# filter.net
KiCad netlist of a schematic drawn in Altium Designer
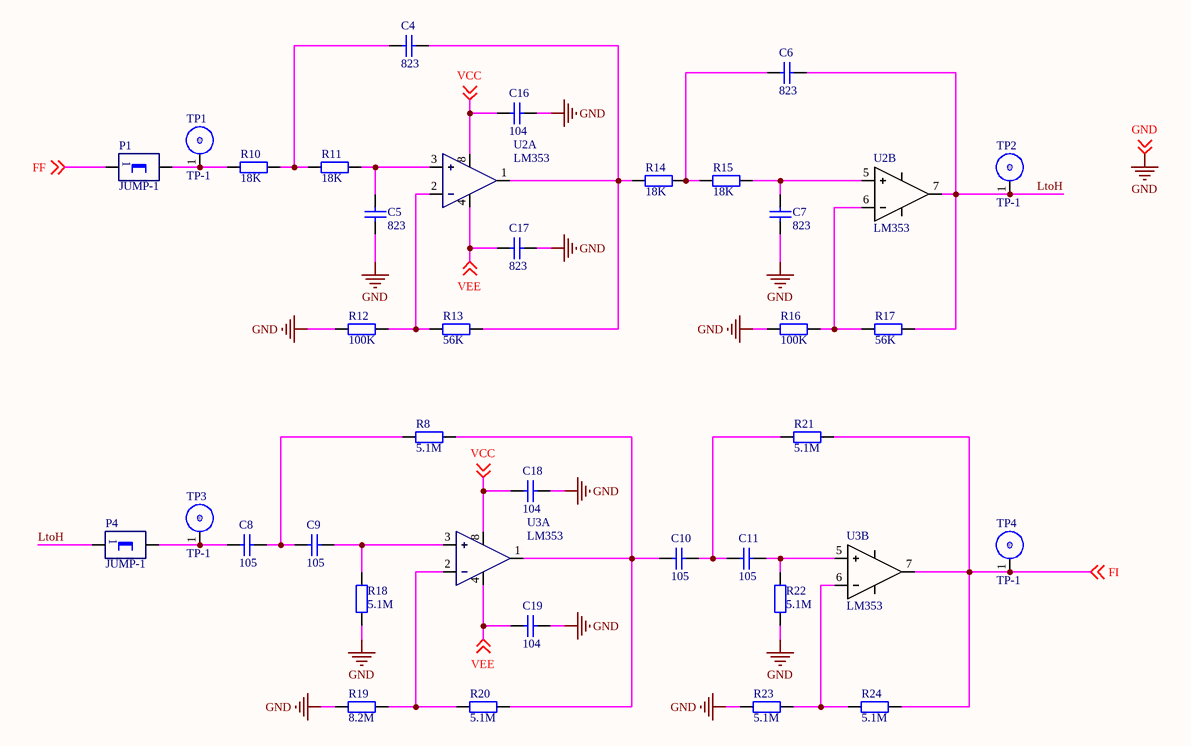
[diagram p0: filter.SchDoc]

(export (version "E")
  (design (tool "Eeschema 10.0.6"))
  (components
    (comp (ref "C4")
      (value "823")
      (footprint "C2")
      (description "Capacitor")
      (fields (field (name "PUBLISHER") "Altium Limited"))
      (libsource (lib "ECG") (part "Cap"))
    )
    (comp (ref "C5")
      (value "823")
      (footprint "C2")
      (description "Capacitor")
      (fields (field (name "PUBLISHER") "Altium Limited"))
      (libsource (lib "ECG") (part "Cap"))
    )
    (comp (ref "C6")
      (value "823")
      (footprint "C2")
      (description "Capacitor")
      (fields (field (name "PUBLISHER") "Altium Limited"))
      (libsource (lib "ECG") (part "Cap"))
    )
    (comp (ref "C7")
      (value "823")
      (footprint "C2")
      (description "Capacitor")
      (fields (field (name "PUBLISHER") "Altium Limited"))
      (libsource (lib "ECG") (part "Cap"))
    )
    (comp (ref "C8")
      (value "105")
      (footprint "C2")
      (description "Capacitor")
      (fields (field (name "PUBLISHER") "Altium Limited"))
      (libsource (lib "ECG") (part "Cap"))
    )
    (comp (ref "C9")
      (value "105")
      (footprint "C2")
      (description "Capacitor")
      (fields (field (name "PUBLISHER") "Altium Limited"))
      (libsource (lib "ECG") (part "Cap"))
    )
    (comp (ref "C10")
      (value "105")
      (footprint "C2")
      (description "Capacitor")
      (fields (field (name "PUBLISHER") "Altium Limited"))
      (libsource (lib "ECG") (part "Cap"))
    )
    (comp (ref "C11")
      (value "105")
      (footprint "C2")
      (description "Capacitor")
      (fields (field (name "PUBLISHER") "Altium Limited"))
      (libsource (lib "ECG") (part "Cap"))
    )
    (comp (ref "C16")
      (value "104")
      (footprint "C2")
      (description "Capacitor")
      (fields (field (name "PUBLISHER") "Altium Limited"))
      (libsource (lib "ECG") (part "Cap"))
    )
    (comp (ref "C17")
      (value "823")
      (footprint "C2")
      (description "Capacitor")
      (fields (field (name "PUBLISHER") "Altium Limited"))
      (libsource (lib "ECG") (part "Cap"))
    )
    (comp (ref "C18")
      (value "104")
      (footprint "C2")
      (description "Capacitor")
      (fields (field (name "PUBLISHER") "Altium Limited"))
      (libsource (lib "ECG") (part "Cap"))
    )
    (comp (ref "C19")
      (value "104")
      (footprint "C2")
      (description "Capacitor")
      (fields (field (name "PUBLISHER") "Altium Limited"))
      (libsource (lib "ECG") (part "Cap"))
    )
    (comp (ref "P1") (value "JUMP-1") (footprint "SIP2") (libsource (lib "ECG") (part "JUMP-1")))
    (comp (ref "P4") (value "JUMP-1") (footprint "SIP2") (libsource (lib "ECG") (part "JUMP-1")))
    (comp (ref "R8")
      (value "5.1M")
      (footprint "AXIAL-0.3")
      (description "Resistor")
      (fields (field (name "PUBLISHER") "Altium Limited"))
      (libsource (lib "") (part "Res2_1"))
    )
    (comp (ref "R10")
      (value "18K")
      (footprint "AXIAL-0.3")
      (description "Resistor")
      (fields (field (name "PUBLISHER") "Altium Limited"))
      (libsource (lib "") (part "Res2_1"))
    )
    (comp (ref "R11")
      (value "18K")
      (footprint "AXIAL-0.3")
      (description "Resistor")
      (fields (field (name "PUBLISHER") "Altium Limited"))
      (libsource (lib "") (part "Res2_1"))
    )
    (comp (ref "R12")
      (value "100K")
      (footprint "AXIAL-0.3")
      (description "Resistor")
      (fields (field (name "PUBLISHER") "Altium Limited"))
      (libsource (lib "") (part "Res2_1"))
    )
    (comp (ref "R13")
      (value "56K")
      (footprint "AXIAL-0.3")
      (description "Resistor")
      (fields (field (name "PUBLISHER") "Altium Limited"))
      (libsource (lib "") (part "Res2_1"))
    )
    (comp (ref "R14")
      (value "18K")
      (footprint "AXIAL-0.3")
      (description "Resistor")
      (fields (field (name "PUBLISHER") "Altium Limited"))
      (libsource (lib "") (part "Res2_1"))
    )
    (comp (ref "R15")
      (value "18K")
      (footprint "AXIAL-0.3")
      (description "Resistor")
      (fields (field (name "PUBLISHER") "Altium Limited"))
      (libsource (lib "") (part "Res2_1"))
    )
    (comp (ref "R16")
      (value "100K")
      (footprint "AXIAL-0.3")
      (description "Resistor")
      (fields (field (name "PUBLISHER") "Altium Limited"))
      (libsource (lib "") (part "Res2_1"))
    )
    (comp (ref "R17")
      (value "56K")
      (footprint "AXIAL-0.3")
      (description "Resistor")
      (fields (field (name "PUBLISHER") "Altium Limited"))
      (libsource (lib "") (part "Res2_1"))
    )
    (comp (ref "R18")
      (value "5.1M")
      (footprint "AXIAL-0.3")
      (description "Resistor")
      (fields (field (name "PUBLISHER") "Altium Limited"))
      (libsource (lib "ECG") (part "Res2"))
    )
    (comp (ref "R19")
      (value "8.2M")
      (footprint "AXIAL-0.3")
      (description "Resistor")
      (fields (field (name "PUBLISHER") "Altium Limited"))
      (libsource (lib "") (part "Res2_1"))
    )
    (comp (ref "R20")
      (value "5.1M")
      (footprint "AXIAL-0.3")
      (description "Resistor")
      (fields (field (name "PUBLISHER") "Altium Limited"))
      (libsource (lib "") (part "Res2_1"))
    )
    (comp (ref "R21")
      (value "5.1M")
      (footprint "AXIAL-0.3")
      (description "Resistor")
      (fields (field (name "PUBLISHER") "Altium Limited"))
      (libsource (lib "") (part "Res2_1"))
    )
    (comp (ref "R22")
      (value "5.1M")
      (footprint "AXIAL-0.3")
      (description "Resistor")
      (fields (field (name "PUBLISHER") "Altium Limited"))
      (libsource (lib "ECG") (part "Res2"))
    )
    (comp (ref "R23")
      (value "5.1M")
      (footprint "AXIAL-0.3")
      (description "Resistor")
      (fields (field (name "PUBLISHER") "Altium Limited"))
      (libsource (lib "") (part "Res2_1"))
    )
    (comp (ref "R24")
      (value "5.1M")
      (footprint "AXIAL-0.3")
      (description "Resistor")
      (fields (field (name "PUBLISHER") "Altium Limited"))
      (libsource (lib "") (part "Res2_1"))
    )
    (comp (ref "TP1") (value "TP-1") (footprint "tp-1-1") (libsource (lib "ECG") (part "TP-1")))
    (comp (ref "TP2") (value "TP-1") (footprint "tp-1-1") (libsource (lib "ECG") (part "TP-1")))
    (comp (ref "TP3") (value "TP-1") (footprint "tp-1-1") (libsource (lib "ECG") (part "TP-1")))
    (comp (ref "TP4") (value "TP-1") (footprint "tp-1-1") (libsource (lib "ECG") (part "TP-1")))
    (comp (ref "U2") (value "LM353") (footprint "DIP8") (libsource (lib "ECG") (part "LM353")))
    (comp (ref "U3") (value "LM353") (footprint "DIP8") (libsource (lib "ECG") (part "LM353")))
  )
  (nets
    (net (code "1") (name "/LtoH") (class "Default")
      (node (ref "C6") (pin "2") (pinfunction "2_2") (pintype "passive"))
      (node (ref "P4") (pin "1") (pinfunction "1_1") (pintype "passive"))
      (node (ref "R17") (pin "2") (pinfunction "2_2") (pintype "passive"))
      (node (ref "TP2") (pin "1") (pintype "passive"))
      (node (ref "U2") (pin "7") (pinfunction "7_7") (pintype "passive"))
    )
    (net (code "2") (name "FF") (class "Default")
      (node (ref "P1") (pin "1") (pinfunction "1_1") (pintype "passive"))
    )
    (net (code "3") (name "FI") (class "Default")
      (node (ref "R21") (pin "2") (pinfunction "2_2") (pintype "passive"))
      (node (ref "R24") (pin "2") (pinfunction "2_2") (pintype "passive"))
      (node (ref "TP4") (pin "1") (pintype "passive"))
      (node (ref "U3") (pin "7") (pinfunction "7_7") (pintype "passive"))
    )
    (net (code "4") (name "GND") (class "Default")
      (node (ref "C16") (pin "2") (pinfunction "2_2") (pintype "passive"))
      (node (ref "C17") (pin "2") (pinfunction "2_2") (pintype "passive"))
      (node (ref "C18") (pin "2") (pinfunction "2_2") (pintype "passive"))
      (node (ref "C19") (pin "2") (pinfunction "2_2") (pintype "passive"))
      (node (ref "C5") (pin "1") (pinfunction "1_1") (pintype "passive"))
      (node (ref "C7") (pin "1") (pinfunction "1_1") (pintype "passive"))
      (node (ref "R12") (pin "1") (pinfunction "1_1") (pintype "passive"))
      (node (ref "R16") (pin "1") (pinfunction "1_1") (pintype "passive"))
      (node (ref "R18") (pin "1") (pinfunction "1_1") (pintype "passive"))
      (node (ref "R19") (pin "1") (pinfunction "1_1") (pintype "passive"))
      (node (ref "R22") (pin "1") (pinfunction "1_1") (pintype "passive"))
      (node (ref "R23") (pin "1") (pinfunction "1_1") (pintype "passive"))
    )
    (net (code "5") (name "Net-(C4-Pad1)") (class "Default")
      (node (ref "C4") (pin "1") (pinfunction "1_1") (pintype "passive"))
      (node (ref "R10") (pin "2") (pinfunction "2_2") (pintype "passive"))
      (node (ref "R11") (pin "1") (pinfunction "1_1") (pintype "passive"))
    )
    (net (code "6") (name "Net-(C4-Pad2)") (class "Default")
      (node (ref "C4") (pin "2") (pinfunction "2_2") (pintype "passive"))
      (node (ref "R13") (pin "2") (pinfunction "2_2") (pintype "passive"))
      (node (ref "R14") (pin "1") (pinfunction "1_1") (pintype "passive"))
      (node (ref "U2") (pin "1") (pinfunction "1_1") (pintype "passive"))
    )
    (net (code "7") (name "Net-(C5-Pad2)") (class "Default")
      (node (ref "C5") (pin "2") (pinfunction "2_2") (pintype "passive"))
      (node (ref "R11") (pin "2") (pinfunction "2_2") (pintype "passive"))
      (node (ref "U2") (pin "3") (pinfunction "3_3") (pintype "passive"))
    )
    (net (code "8") (name "Net-(C6-Pad1)") (class "Default")
      (node (ref "C6") (pin "1") (pinfunction "1_1") (pintype "passive"))
      (node (ref "R14") (pin "2") (pinfunction "2_2") (pintype "passive"))
      (node (ref "R15") (pin "1") (pinfunction "1_1") (pintype "passive"))
    )
    (net (code "9") (name "Net-(C7-Pad2)") (class "Default")
      (node (ref "C7") (pin "2") (pinfunction "2_2") (pintype "passive"))
      (node (ref "R15") (pin "2") (pinfunction "2_2") (pintype "passive"))
      (node (ref "U2") (pin "5") (pinfunction "5_5") (pintype "passive"))
    )
    (net (code "10") (name "Net-(C8-Pad1)") (class "Default")
      (node (ref "C8") (pin "1") (pinfunction "1_1") (pintype "passive"))
      (node (ref "P4") (pin "2") (pintype "passive"))
      (node (ref "TP3") (pin "1") (pintype "passive"))
    )
    (net (code "11") (name "Net-(C8-Pad2)") (class "Default")
      (node (ref "C8") (pin "2") (pinfunction "2_2") (pintype "passive"))
      (node (ref "C9") (pin "1") (pinfunction "1_1") (pintype "passive"))
      (node (ref "R8") (pin "1") (pinfunction "1_1") (pintype "passive"))
    )
    (net (code "12") (name "Net-(C9-Pad2)") (class "Default")
      (node (ref "C9") (pin "2") (pinfunction "2_2") (pintype "passive"))
      (node (ref "R18") (pin "2") (pinfunction "2_2") (pintype "passive"))
      (node (ref "U3") (pin "3") (pinfunction "3_3") (pintype "passive"))
    )
    (net (code "13") (name "Net-(C10-Pad1)") (class "Default")
      (node (ref "C10") (pin "1") (pinfunction "1_1") (pintype "passive"))
      (node (ref "R20") (pin "2") (pinfunction "2_2") (pintype "passive"))
      (node (ref "R8") (pin "2") (pinfunction "2_2") (pintype "passive"))
      (node (ref "U3") (pin "1") (pinfunction "1_1") (pintype "passive"))
    )
    (net (code "14") (name "Net-(C10-Pad2)") (class "Default")
      (node (ref "C10") (pin "2") (pinfunction "2_2") (pintype "passive"))
      (node (ref "C11") (pin "1") (pinfunction "1_1") (pintype "passive"))
      (node (ref "R21") (pin "1") (pinfunction "1_1") (pintype "passive"))
    )
    (net (code "15") (name "Net-(C11-Pad2)") (class "Default")
      (node (ref "C11") (pin "2") (pinfunction "2_2") (pintype "passive"))
      (node (ref "R22") (pin "2") (pinfunction "2_2") (pintype "passive"))
      (node (ref "U3") (pin "5") (pinfunction "5_5") (pintype "passive"))
    )
    (net (code "16") (name "Net-(P1-Pad2)") (class "Default")
      (node (ref "P1") (pin "2") (pintype "passive"))
      (node (ref "R10") (pin "1") (pinfunction "1_1") (pintype "passive"))
      (node (ref "TP1") (pin "1") (pintype "passive"))
    )
    (net (code "17") (name "Net-(R12-Pad2)") (class "Default")
      (node (ref "R12") (pin "2") (pinfunction "2_2") (pintype "passive"))
      (node (ref "R13") (pin "1") (pinfunction "1_1") (pintype "passive"))
      (node (ref "U2") (pin "2") (pinfunction "2_2") (pintype "passive"))
    )
    (net (code "18") (name "Net-(R16-Pad2)") (class "Default")
      (node (ref "R16") (pin "2") (pinfunction "2_2") (pintype "passive"))
      (node (ref "R17") (pin "1") (pinfunction "1_1") (pintype "passive"))
      (node (ref "U2") (pin "6") (pinfunction "6_6") (pintype "passive"))
    )
    (net (code "19") (name "Net-(R19-Pad2)") (class "Default")
      (node (ref "R19") (pin "2") (pinfunction "2_2") (pintype "passive"))
      (node (ref "R20") (pin "1") (pinfunction "1_1") (pintype "passive"))
      (node (ref "U3") (pin "2") (pinfunction "2_2") (pintype "passive"))
    )
    (net (code "20") (name "Net-(R23-Pad2)") (class "Default")
      (node (ref "R23") (pin "2") (pinfunction "2_2") (pintype "passive"))
      (node (ref "R24") (pin "1") (pinfunction "1_1") (pintype "passive"))
      (node (ref "U3") (pin "6") (pinfunction "6_6") (pintype "passive"))
    )
    (net (code "21") (name "VCC") (class "Default")
      (node (ref "C16") (pin "1") (pinfunction "1_1") (pintype "passive"))
      (node (ref "C18") (pin "1") (pinfunction "1_1") (pintype "passive"))
      (node (ref "U2") (pin "8") (pinfunction "8_8") (pintype "passive"))
      (node (ref "U3") (pin "8") (pinfunction "8_8") (pintype "passive"))
    )
    (net (code "22") (name "VEE") (class "Default")
      (node (ref "C17") (pin "1") (pinfunction "1_1") (pintype "passive"))
      (node (ref "C19") (pin "1") (pinfunction "1_1") (pintype "passive"))
      (node (ref "U2") (pin "4") (pinfunction "4_4") (pintype "passive"))
      (node (ref "U3") (pin "4") (pinfunction "4_4") (pintype "passive"))
    )
  )
)
